# CPU.net
KiCad netlist of a schematic drawn in Altium Designer
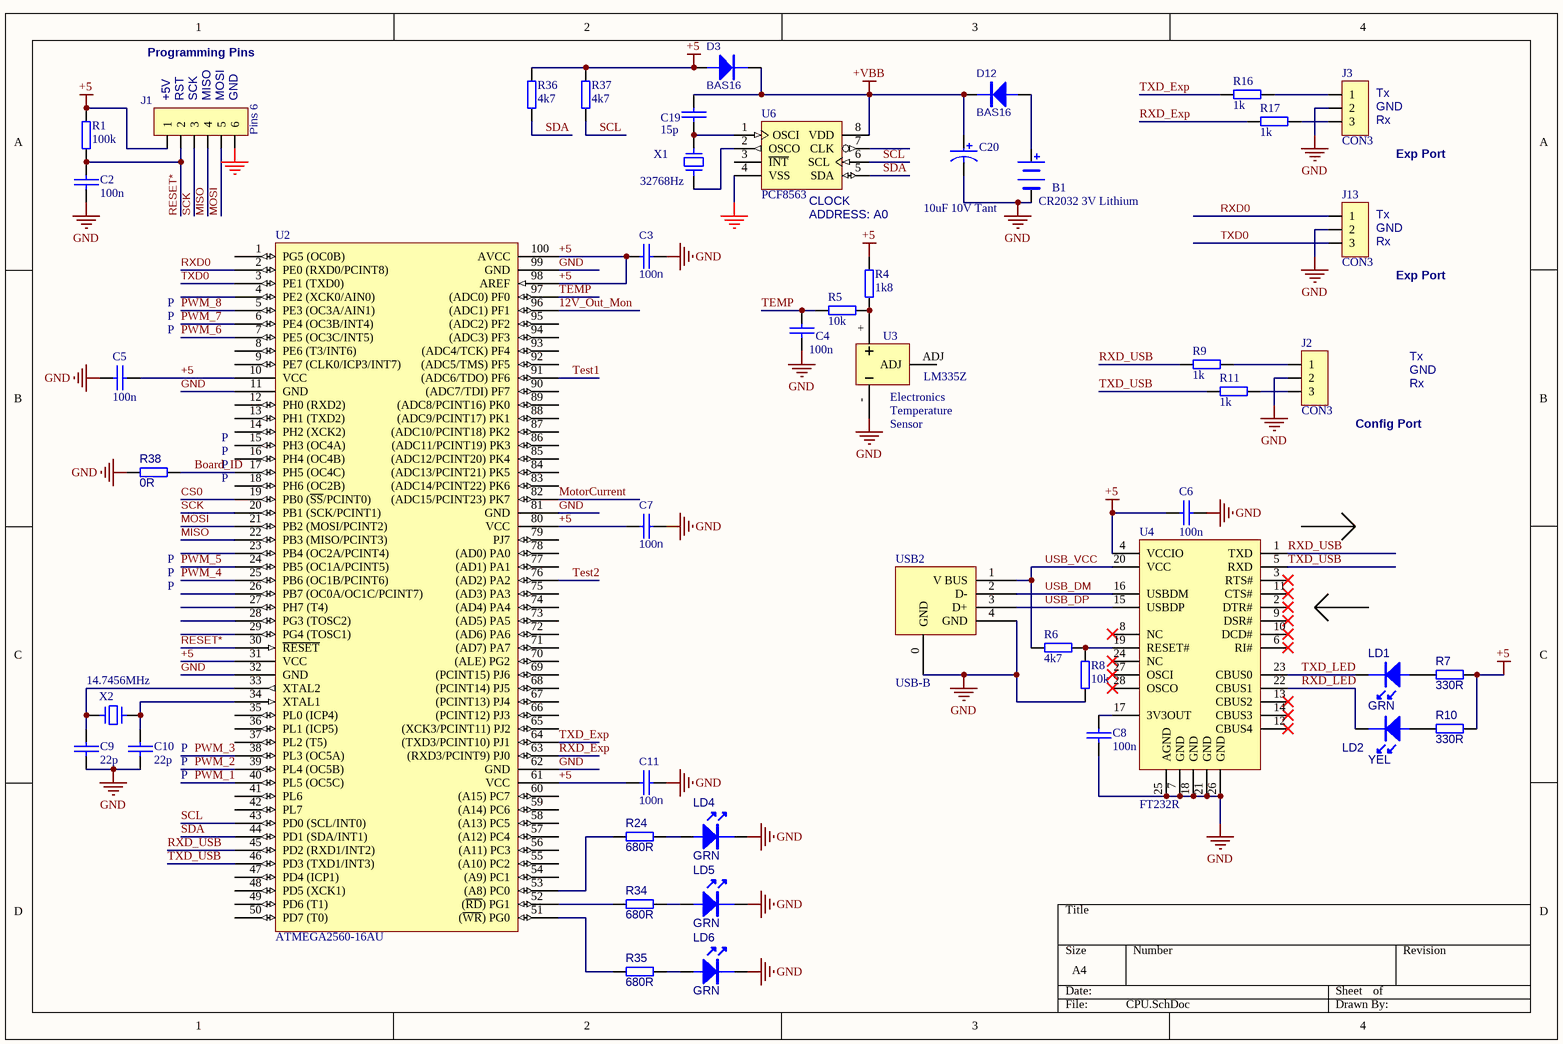
[diagram p0: CPU.SchDoc]

(export (version "E")
  (design (tool "Eeschema 10.0.6"))
  (components
    (comp (ref "B1")
      (value "CR2032 3V Lithium")
      (footprint "COINBATT6")
      (libsource (lib "*") (part "BATTERY"))
    )
    (comp (ref "C2") (value "100n") (footprint "0603") (libsource (lib "DEVICE") (part "CAP")))
    (comp (ref "C3") (value "100n") (footprint "0603") (libsource (lib "*") (part "CAP")))
    (comp (ref "C4") (value "100n") (footprint "0603") (libsource (lib "DEVICE") (part "CAP")))
    (comp (ref "C5") (value "100n") (footprint "0603") (libsource (lib "DEVICE") (part "CAP")))
    (comp (ref "C6") (value "100n") (footprint "0603") (libsource (lib "") (part "CAP_1")))
    (comp (ref "C7") (value "100n") (footprint "0603") (libsource (lib "*") (part "CAP")))
    (comp (ref "C8") (value "100n") (footprint "0603") (libsource (lib "") (part "CAP_1")))
    (comp (ref "C9") (value "22p") (footprint "0603") (libsource (lib "DEVICE") (part "CAP")))
    (comp (ref "C10") (value "22p") (footprint "0603") (libsource (lib "DEVICE") (part "CAP")))
    (comp (ref "C11") (value "100n") (footprint "0603") (libsource (lib "*") (part "CAP")))
    (comp (ref "C19") (value "15p") (footprint "0603") (libsource (lib "") (part "CAP_1")))
    (comp (ref "C20")
      (value "10uF 10V Tant")
      (footprint "SMD-TANT-A")
      (libsource (lib "DEVICE") (part "CAPACITOR POL-S"))
    )
    (comp (ref "D3") (value "BAS16") (footprint "SOT-23-bat54") (libsource (lib "*") (part "DIODE")))
    (comp (ref "D12") (value "BAS16") (footprint "SOT-23-bat54") (libsource (lib "*") (part "DIODE")))
    (comp (ref "J1") (value "Pins 6") (footprint "SIP6") (libsource (lib "*") (part "CON6")))
    (comp (ref "J2") (value "CON3") (footprint "SIP3") (libsource (lib "DEVICE") (part "CON3")))
    (comp (ref "J3") (value "CON3") (footprint "SIP3") (libsource (lib "DEVICE") (part "CON3")))
    (comp (ref "J13") (value "CON3") (footprint "SIP3") (libsource (lib "DEVICE") (part "CON3")))
    (comp (ref "LD1") (value "GRN") (footprint "0805DIODE") (libsource (lib "*") (part "LED")))
    (comp (ref "LD2") (value "YEL") (footprint "0805DIODE") (libsource (lib "*") (part "LED")))
    (comp (ref "LD4") (value "GRN") (footprint "0805DIODE") (libsource (lib "*") (part "LED")))
    (comp (ref "LD5") (value "GRN") (footprint "0805DIODE") (libsource (lib "*") (part "LED")))
    (comp (ref "LD6") (value "GRN") (footprint "0805DIODE") (libsource (lib "*") (part "LED")))
    (comp (ref "R1") (value "100k") (footprint "0603") (libsource (lib "DEVICE") (part "RES8")))
    (comp (ref "R4") (value "1k8") (footprint "0603") (libsource (lib "DEVICE") (part "RES8")))
    (comp (ref "R5") (value "10k") (footprint "0603") (libsource (lib "DEVICE") (part "RES8")))
    (comp (ref "R6") (value "4k7") (footprint "0603") (libsource (lib "DEVICE") (part "RES8")))
    (comp (ref "R7") (value "330R") (footprint "0603") (libsource (lib "DEVICE") (part "RES8")))
    (comp (ref "R8") (value "10k") (footprint "0603") (libsource (lib "DEVICE") (part "RES8")))
    (comp (ref "R9") (value "1k") (footprint "0603") (libsource (lib "DEVICE") (part "RES8")))
    (comp (ref "R10") (value "330R") (footprint "0603") (libsource (lib "DEVICE") (part "RES8")))
    (comp (ref "R11") (value "1k") (footprint "0603") (libsource (lib "DEVICE") (part "RES8")))
    (comp (ref "R16") (value "1k") (footprint "0603") (libsource (lib "DEVICE") (part "RES8")))
    (comp (ref "R17") (value "1k") (footprint "0603") (libsource (lib "DEVICE") (part "RES8")))
    (comp (ref "R24") (value "680R") (footprint "0603") (libsource (lib "DEVICE") (part "RES8")))
    (comp (ref "R34") (value "680R") (footprint "0603") (libsource (lib "DEVICE") (part "RES8")))
    (comp (ref "R35") (value "680R") (footprint "0603") (libsource (lib "DEVICE") (part "RES8")))
    (comp (ref "R36") (value "4k7") (footprint "0603") (libsource (lib "DEVICE") (part "RES8")))
    (comp (ref "R37") (value "4k7") (footprint "0603") (libsource (lib "DEVICE") (part "RES8")))
    (comp (ref "R38") (value "0R") (footprint "0603") (libsource (lib "DEVICE") (part "RES8")))
    (comp (ref "U2")
      (value "ATMEGA2560-16AU")
      (footprint "100T1_N")
      (libsource (lib "Atmel") (part "ATMEGA2560(TQFP100)"))
    )
    (comp (ref "U3") (value "LM335Z") (footprint "TO-92_LM335") (libsource (lib "D_LINEAR") (part "LM335Z")))
    (comp (ref "U4") (value "FT232R") (footprint "ssop28") (libsource (lib "FTDI") (part "FT232R")))
    (comp (ref "U6") (value "PCF8563") (footprint "so-8") (libsource (lib "PHILIPS") (part "PCF8563")))
    (comp (ref "USB2") (value "USB-B") (footprint "USB_BV") (libsource (lib "DEVICE") (part "USB-B")))
    (comp (ref "X1") (value "32768Hz") (footprint "XTAL32K") (libsource (lib "*") (part "CRYSTAL")))
    (comp (ref "X2") (value "14.7456MHz") (footprint "XTAL-V2") (libsource (lib "DEVICE") (part "CRYSTAL")))
  )
  (nets
    (net (code "1") (name "+5") (class "Default")
      (node (ref "C11") (pin "2") (pintype "passive"))
      (node (ref "C3") (pin "2") (pintype "passive"))
      (node (ref "C5") (pin "1") (pintype "passive"))
      (node (ref "C6") (pin "2") (pintype "passive"))
      (node (ref "C7") (pin "2") (pintype "passive"))
      (node (ref "D3") (pin "A") (pinfunction "A_A") (pintype "passive"))
      (node (ref "J1") (pin "1") (pinfunction "1_1") (pintype "passive"))
      (node (ref "R1") (pin "2") (pintype "passive"))
      (node (ref "R10") (pin "1") (pintype "passive"))
      (node (ref "R36") (pin "2") (pintype "passive"))
      (node (ref "R37") (pin "2") (pintype "passive"))
      (node (ref "R4") (pin "1") (pintype "passive"))
      (node (ref "R7") (pin "1") (pintype "passive"))
      (node (ref "U2") (pin "10") (pinfunction "VCC_10") (pintype "power_in"))
      (node (ref "U2") (pin "100") (pinfunction "AVCC_100") (pintype "power_in"))
      (node (ref "U2") (pin "31") (pinfunction "VCC_31") (pintype "power_in"))
      (node (ref "U2") (pin "61") (pinfunction "VCC_61") (pintype "power_in"))
      (node (ref "U2") (pin "80") (pinfunction "VCC_80") (pintype "power_in"))
      (node (ref "U2") (pin "98") (pinfunction "AREF_98") (pintype "input"))
      (node (ref "U4") (pin "4") (pinfunction "VCCIO_4") (pintype "passive"))
    )
    (net (code "2") (name "+VBB") (class "Default")
      (node (ref "C19") (pin "1") (pintype "passive"))
      (node (ref "C20") (pin "1") (pinfunction "1_1") (pintype "passive"))
      (node (ref "D12") (pin "K") (pinfunction "K_K") (pintype "passive"))
      (node (ref "D3") (pin "K") (pinfunction "K_K") (pintype "passive"))
      (node (ref "U6") (pin "8") (pinfunction "VDD_8") (pintype "power_in"))
    )
    (net (code "3") (name "/12V_Out_Mon") (class "Default")
      (node (ref "U2") (pin "96") (pinfunction "(ADC1)_PF1_96") (pintype "bidirectional"))
    )
    (net (code "4") (name "/Board_ID") (class "Default")
      (node (ref "R38") (pin "2") (pintype "passive"))
      (node (ref "U2") (pin "17") (pinfunction "PH5_(OC4C)_17") (pintype "bidirectional"))
    )
    (net (code "5") (name "/CS0") (class "Default")
      (node (ref "U2") (pin "19") (pinfunction "PB0_(~{SS}/PCINT0)_19") (pintype "bidirectional"))
    )
    (net (code "6") (name "/MISO") (class "Default")
      (node (ref "J1") (pin "4") (pinfunction "4_4") (pintype "passive"))
      (node (ref "U2") (pin "22") (pinfunction "PB3_(MISO/PCINT3)_22") (pintype "bidirectional"))
    )
    (net (code "7") (name "/MOSI") (class "Default")
      (node (ref "J1") (pin "5") (pinfunction "5_5") (pintype "passive"))
      (node (ref "U2") (pin "21") (pinfunction "PB2_(MOSI/PCINT2)_21") (pintype "bidirectional"))
    )
    (net (code "8") (name "/MotorCurrent") (class "Default")
      (node (ref "U2") (pin "82") (pinfunction "(ADC15/PCINT23)_PK7_82") (pintype "bidirectional"))
    )
    (net (code "9") (name "/PWM_1") (class "Default")
      (node (ref "U2") (pin "40") (pinfunction "PL5_(OC5C)_40") (pintype "bidirectional"))
    )
    (net (code "10") (name "/PWM_2") (class "Default")
      (node (ref "U2") (pin "39") (pinfunction "PL4_(OC5B)_39") (pintype "bidirectional"))
    )
    (net (code "11") (name "/PWM_3") (class "Default")
      (node (ref "U2") (pin "38") (pinfunction "PL3_(OC5A)_38") (pintype "bidirectional"))
    )
    (net (code "12") (name "/PWM_4") (class "Default")
      (node (ref "U2") (pin "25") (pinfunction "PB6_(OC1B/PCINT6)_25") (pintype "bidirectional"))
    )
    (net (code "13") (name "/PWM_5") (class "Default")
      (node (ref "U2") (pin "24") (pinfunction "PB5_(OC1A/PCINT5)_24") (pintype "bidirectional"))
    )
    (net (code "14") (name "/PWM_6") (class "Default")
      (node (ref "U2") (pin "7") (pinfunction "PE5_(OC3C/INT5)_7") (pintype "bidirectional"))
    )
    (net (code "15") (name "/PWM_7") (class "Default")
      (node (ref "U2") (pin "6") (pinfunction "PE4_(OC3B/INT4)_6") (pintype "bidirectional"))
    )
    (net (code "16") (name "/PWM_8") (class "Default")
      (node (ref "U2") (pin "5") (pinfunction "PE3_(OC3A/AIN1)_5") (pintype "bidirectional"))
    )
    (net (code "17") (name "/RESET*") (class "Default")
      (node (ref "C2") (pin "2") (pintype "passive"))
      (node (ref "J1") (pin "2") (pinfunction "2_2") (pintype "passive"))
      (node (ref "R1") (pin "1") (pintype "passive"))
      (node (ref "U2") (pin "30") (pinfunction "~{RESET}_30") (pintype "input"))
    )
    (net (code "18") (name "/RXD0") (class "Default")
      (node (ref "J13") (pin "1") (pinfunction "1_1") (pintype "passive"))
      (node (ref "U2") (pin "2") (pinfunction "PE0_(RXD0/PCINT8)_2") (pintype "bidirectional"))
    )
    (net (code "19") (name "/RXD_Exp") (class "Default")
      (node (ref "R17") (pin "1") (pintype "passive"))
      (node (ref "U2") (pin "63") (pinfunction "(RXD3/PCINT9)_PJ0_63") (pintype "bidirectional"))
    )
    (net (code "20") (name "/RXD_LED") (class "Default")
      (node (ref "LD2") (pin "K") (pintype "passive"))
      (node (ref "U4") (pin "22") (pinfunction "CBUS1_22") (pintype "passive"))
    )
    (net (code "21") (name "/RXD_USB") (class "Default")
      (node (ref "R9") (pin "1") (pintype "passive"))
      (node (ref "U2") (pin "45") (pinfunction "PD2_(RXD1/INT2)_45") (pintype "bidirectional"))
      (node (ref "U4") (pin "1") (pinfunction "TXD_1") (pintype "passive"))
    )
    (net (code "22") (name "/SCK") (class "Default")
      (node (ref "J1") (pin "3") (pinfunction "3_3") (pintype "passive"))
      (node (ref "U2") (pin "20") (pinfunction "PB1_(SCK/PCINT1)_20") (pintype "bidirectional"))
    )
    (net (code "23") (name "/SCL") (class "Default")
      (node (ref "R37") (pin "1") (pintype "passive"))
      (node (ref "U2") (pin "43") (pinfunction "PD0_(SCL/INT0)_43") (pintype "bidirectional"))
      (node (ref "U6") (pin "6") (pinfunction "SCL_6") (pintype "input"))
    )
    (net (code "24") (name "/SDA") (class "Default")
      (node (ref "R36") (pin "1") (pintype "passive"))
      (node (ref "U2") (pin "44") (pinfunction "PD1_(SDA/INT1)_44") (pintype "bidirectional"))
      (node (ref "U6") (pin "5") (pinfunction "SDA_5") (pintype "bidirectional"))
    )
    (net (code "25") (name "/TEMP") (class "Default")
      (node (ref "C4") (pin "1") (pintype "passive"))
      (node (ref "R5") (pin "1") (pintype "passive"))
      (node (ref "U2") (pin "97") (pinfunction "(ADC0)_PF0_97") (pintype "bidirectional"))
    )
    (net (code "26") (name "/TXD0") (class "Default")
      (node (ref "J13") (pin "3") (pinfunction "3_3") (pintype "passive"))
      (node (ref "U2") (pin "3") (pinfunction "PE1_(TXD0)_3") (pintype "bidirectional"))
    )
    (net (code "27") (name "/TXD_Exp") (class "Default")
      (node (ref "R16") (pin "1") (pintype "passive"))
      (node (ref "U2") (pin "64") (pinfunction "(TXD3/PCINT10)_PJ1_64") (pintype "bidirectional"))
    )
    (net (code "28") (name "/TXD_LED") (class "Default")
      (node (ref "LD1") (pin "K") (pintype "passive"))
      (node (ref "U4") (pin "23") (pinfunction "CBUS0_23") (pintype "passive"))
    )
    (net (code "29") (name "/TXD_USB") (class "Default")
      (node (ref "R11") (pin "1") (pintype "passive"))
      (node (ref "U2") (pin "46") (pinfunction "PD3_(TXD1/INT3)_46") (pintype "bidirectional"))
      (node (ref "U4") (pin "5") (pinfunction "RXD_5") (pintype "passive"))
    )
    (net (code "30") (name "/Test1") (class "Default")
      (node (ref "U2") (pin "91") (pinfunction "(ADC6/TDO)_PF6_91") (pintype "bidirectional"))
    )
    (net (code "31") (name "/Test2") (class "Default")
      (node (ref "U2") (pin "76") (pinfunction "(AD2)_PA2_76") (pintype "bidirectional"))
    )
    (net (code "32") (name "/USB_DM") (class "Default")
      (node (ref "U4") (pin "16") (pinfunction "USBDM_16") (pintype "passive"))
      (node (ref "USB2") (pin "2") (pinfunction "D-_2") (pintype "passive"))
    )
    (net (code "33") (name "/USB_DP") (class "Default")
      (node (ref "U4") (pin "15") (pinfunction "USBDP_15") (pintype "passive"))
      (node (ref "USB2") (pin "3") (pinfunction "D+_3") (pintype "passive"))
    )
    (net (code "34") (name "/USB_VCC") (class "Default")
      (node (ref "R6") (pin "1") (pintype "passive"))
      (node (ref "U4") (pin "20") (pinfunction "VCC_20") (pintype "passive"))
      (node (ref "USB2") (pin "1") (pinfunction "V_BUS_1") (pintype "passive"))
    )
    (net (code "35") (name "GND") (class "Default")
      (node (ref "B1") (pin "-") (pinfunction "-_-") (pintype "passive"))
      (node (ref "C10") (pin "2") (pintype "passive"))
      (node (ref "C11") (pin "1") (pintype "passive"))
      (node (ref "C2") (pin "1") (pintype "passive"))
      (node (ref "C20") (pin "2") (pinfunction "2_2") (pintype "passive"))
      (node (ref "C3") (pin "1") (pintype "passive"))
      (node (ref "C4") (pin "2") (pintype "passive"))
      (node (ref "C5") (pin "2") (pintype "passive"))
      (node (ref "C6") (pin "1") (pintype "passive"))
      (node (ref "C7") (pin "1") (pintype "passive"))
      (node (ref "C8") (pin "1") (pintype "passive"))
      (node (ref "C9") (pin "2") (pintype "passive"))
      (node (ref "J1") (pin "6") (pinfunction "6_6") (pintype "passive"))
      (node (ref "J13") (pin "2") (pinfunction "2_2") (pintype "passive"))
      (node (ref "J2") (pin "2") (pinfunction "2_2") (pintype "passive"))
      (node (ref "J3") (pin "2") (pinfunction "2_2") (pintype "passive"))
      (node (ref "LD4") (pin "K") (pintype "passive"))
      (node (ref "LD5") (pin "K") (pintype "passive"))
      (node (ref "LD6") (pin "K") (pintype "passive"))
      (node (ref "R38") (pin "1") (pintype "passive"))
      (node (ref "R8") (pin "1") (pintype "passive"))
      (node (ref "U2") (pin "11") (pinfunction "GND_11") (pintype "power_in"))
      (node (ref "U2") (pin "32") (pinfunction "GND_32") (pintype "power_in"))
      (node (ref "U2") (pin "62") (pinfunction "GND_62") (pintype "power_in"))
      (node (ref "U2") (pin "81") (pinfunction "GND_81") (pintype "power_in"))
      (node (ref "U2") (pin "99") (pinfunction "GND_99") (pintype "power_in"))
      (node (ref "U3") (pin "-") (pinfunction "-_-") (pintype "passive"))
      (node (ref "U4") (pin "18") (pinfunction "GND_18") (pintype "passive"))
      (node (ref "U4") (pin "21") (pinfunction "GND_21") (pintype "passive"))
      (node (ref "U4") (pin "25") (pinfunction "AGND_25") (pintype "passive"))
      (node (ref "U4") (pin "26") (pinfunction "GND_26") (pintype "passive"))
      (node (ref "U4") (pin "7") (pinfunction "GND_7") (pintype "passive"))
      (node (ref "U6") (pin "4") (pinfunction "VSS_4") (pintype "power_in"))
      (node (ref "USB2") (pin "0") (pinfunction "GND_0") (pintype "power_in"))
      (node (ref "USB2") (pin "4") (pinfunction "GND_4") (pintype "passive"))
    )
    (net (code "36") (name "Net-(B1-Pad+)") (class "Default")
      (node (ref "B1") (pin "+") (pinfunction "+_+") (pintype "passive"))
      (node (ref "D12") (pin "A") (pinfunction "A_A") (pintype "passive"))
    )
    (net (code "37") (name "Net-(J2-Pad1)") (class "Default")
      (node (ref "J2") (pin "1") (pinfunction "1_1") (pintype "passive"))
      (node (ref "R9") (pin "2") (pintype "passive"))
    )
    (net (code "38") (name "Net-(J2-Pad3)") (class "Default")
      (node (ref "J2") (pin "3") (pinfunction "3_3") (pintype "passive"))
      (node (ref "R11") (pin "2") (pintype "passive"))
    )
    (net (code "39") (name "Net-(J3-Pad1)") (class "Default")
      (node (ref "J3") (pin "1") (pinfunction "1_1") (pintype "passive"))
      (node (ref "R16") (pin "2") (pintype "passive"))
    )
    (net (code "40") (name "Net-(J3-Pad3)") (class "Default")
      (node (ref "J3") (pin "3") (pinfunction "3_3") (pintype "passive"))
      (node (ref "R17") (pin "2") (pintype "passive"))
    )
    (net (code "41") (name "Net-(LD1-PadA)") (class "Default")
      (node (ref "LD1") (pin "A") (pintype "passive"))
      (node (ref "R7") (pin "2") (pintype "passive"))
    )
    (net (code "42") (name "Net-(LD2-PadA)") (class "Default")
      (node (ref "LD2") (pin "A") (pintype "passive"))
      (node (ref "R10") (pin "2") (pintype "passive"))
    )
    (net (code "43") (name "Net-(LD4-PadA)") (class "Default")
      (node (ref "LD4") (pin "A") (pintype "passive"))
      (node (ref "R24") (pin "2") (pintype "passive"))
    )
    (net (code "44") (name "Net-(LD5-PadA)") (class "Default")
      (node (ref "LD5") (pin "A") (pintype "passive"))
      (node (ref "R34") (pin "2") (pintype "passive"))
    )
    (net (code "45") (name "Net-(LD6-PadA)") (class "Default")
      (node (ref "LD6") (pin "A") (pintype "passive"))
      (node (ref "R35") (pin "2") (pintype "passive"))
    )
    (net (code "46") (name "Net-(R4-Pad2)") (class "Default")
      (node (ref "R4") (pin "2") (pintype "passive"))
      (node (ref "R5") (pin "2") (pintype "passive"))
      (node (ref "U3") (pin "+") (pinfunction "+_+") (pintype "passive"))
    )
    (net (code "47") (name "Net-(U2-(A8)_PC0)") (class "Default")
      (node (ref "R24") (pin "1") (pintype "passive"))
      (node (ref "U2") (pin "53") (pinfunction "(A8)_PC0_53") (pintype "bidirectional"))
    )
    (net (code "48") (name "Net-(U2-(~{RD})_PG1)") (class "Default")
      (node (ref "R34") (pin "1") (pintype "passive"))
      (node (ref "U2") (pin "52") (pinfunction "(~{RD})_PG1_52") (pintype "bidirectional"))
    )
    (net (code "49") (name "Net-(U2-(~{WR})_PG0)") (class "Default")
      (node (ref "R35") (pin "1") (pintype "passive"))
      (node (ref "U2") (pin "51") (pinfunction "(~{WR})_PG0_51") (pintype "bidirectional"))
    )
    (net (code "50") (name "Net-(U2-XTAL1)") (class "Default")
      (node (ref "C10") (pin "1") (pintype "passive"))
      (node (ref "U2") (pin "34") (pinfunction "XTAL1_34") (pintype "input"))
      (node (ref "X2") (pin "1") (pintype "passive"))
    )
    (net (code "51") (name "Net-(U2-XTAL2)") (class "Default")
      (node (ref "C9") (pin "1") (pintype "passive"))
      (node (ref "U2") (pin "33") (pinfunction "XTAL2_33") (pintype "output"))
      (node (ref "X2") (pin "2") (pintype "passive"))
    )
    (net (code "52") (name "Net-(U4-3V3OUT)") (class "Default")
      (node (ref "C8") (pin "2") (pintype "passive"))
      (node (ref "U4") (pin "17") (pinfunction "3V3OUT_17") (pintype "passive"))
    )
    (net (code "53") (name "Net-(U4-RESET#)") (class "Default")
      (node (ref "R6") (pin "2") (pintype "passive"))
      (node (ref "R8") (pin "2") (pintype "passive"))
      (node (ref "U4") (pin "19") (pinfunction "RESET#_19") (pintype "passive"))
    )
    (net (code "54") (name "Net-(U6-OSCI)") (class "Default")
      (node (ref "C19") (pin "2") (pintype "passive"))
      (node (ref "U6") (pin "1") (pinfunction "OSCI_1") (pintype "input"))
      (node (ref "X1") (pin "2") (pintype "passive"))
    )
    (net (code "55") (name "Net-(U6-OSCO)") (class "Default")
      (node (ref "U6") (pin "2") (pinfunction "OSCO_2") (pintype "output"))
      (node (ref "X1") (pin "1") (pintype "passive"))
    )
    (net (code "56") (name "unconnected-(U2-(A9)_PC1-Pad54)") (class "Default")
      (node (ref "U2") (pin "54") (pinfunction "(A9)_PC1_54") (pintype "bidirectional"))
    )
    (net (code "57") (name "unconnected-(U2-(A10)_PC2-Pad55)") (class "Default")
      (node (ref "U2") (pin "55") (pinfunction "(A10)_PC2_55") (pintype "bidirectional"))
    )
    (net (code "58") (name "unconnected-(U2-(A11)_PC3-Pad56)") (class "Default")
      (node (ref "U2") (pin "56") (pinfunction "(A11)_PC3_56") (pintype "bidirectional"))
    )
    (net (code "59") (name "unconnected-(U2-(A12)_PC4-Pad57)") (class "Default")
      (node (ref "U2") (pin "57") (pinfunction "(A12)_PC4_57") (pintype "bidirectional"))
    )
    (net (code "60") (name "unconnected-(U2-(A13)_PC5-Pad58)") (class "Default")
      (node (ref "U2") (pin "58") (pinfunction "(A13)_PC5_58") (pintype "bidirectional"))
    )
    (net (code "61") (name "unconnected-(U2-(A14)_PC6-Pad59)") (class "Default")
      (node (ref "U2") (pin "59") (pinfunction "(A14)_PC6_59") (pintype "bidirectional"))
    )
    (net (code "62") (name "unconnected-(U2-(A15)_PC7-Pad60)") (class "Default")
      (node (ref "U2") (pin "60") (pinfunction "(A15)_PC7_60") (pintype "bidirectional"))
    )
    (net (code "63") (name "unconnected-(U2-(AD0)_PA0-Pad78)") (class "Default")
      (node (ref "U2") (pin "78") (pinfunction "(AD0)_PA0_78") (pintype "bidirectional"))
    )
    (net (code "64") (name "unconnected-(U2-(AD1)_PA1-Pad77)") (class "Default")
      (node (ref "U2") (pin "77") (pinfunction "(AD1)_PA1_77") (pintype "bidirectional"))
    )
    (net (code "65") (name "unconnected-(U2-(AD3)_PA3-Pad75)") (class "Default")
      (node (ref "U2") (pin "75") (pinfunction "(AD3)_PA3_75") (pintype "bidirectional"))
    )
    (net (code "66") (name "unconnected-(U2-(AD4)_PA4-Pad74)") (class "Default")
      (node (ref "U2") (pin "74") (pinfunction "(AD4)_PA4_74") (pintype "bidirectional"))
    )
    (net (code "67") (name "unconnected-(U2-(AD5)_PA5-Pad73)") (class "Default")
      (node (ref "U2") (pin "73") (pinfunction "(AD5)_PA5_73") (pintype "bidirectional"))
    )
    (net (code "68") (name "unconnected-(U2-(AD6)_PA6-Pad72)") (class "Default")
      (node (ref "U2") (pin "72") (pinfunction "(AD6)_PA6_72") (pintype "bidirectional"))
    )
    (net (code "69") (name "unconnected-(U2-(AD7)_PA7-Pad71)") (class "Default")
      (node (ref "U2") (pin "71") (pinfunction "(AD7)_PA7_71") (pintype "bidirectional"))
    )
    (net (code "70") (name "unconnected-(U2-(ADC2)_PF2-Pad95)") (class "Default")
      (node (ref "U2") (pin "95") (pinfunction "(ADC2)_PF2_95") (pintype "bidirectional"))
    )
    (net (code "71") (name "unconnected-(U2-(ADC3)_PF3-Pad94)") (class "Default")
      (node (ref "U2") (pin "94") (pinfunction "(ADC3)_PF3_94") (pintype "bidirectional"))
    )
    (net (code "72") (name "unconnected-(U2-(ADC4{slash}TCK)_PF4-Pad93)") (class "Default")
      (node (ref "U2") (pin "93") (pinfunction "(ADC4/TCK)_PF4_93") (pintype "bidirectional"))
    )
    (net (code "73") (name "unconnected-(U2-(ADC5{slash}TMS)_PF5-Pad92)") (class "Default")
      (node (ref "U2") (pin "92") (pinfunction "(ADC5/TMS)_PF5_92") (pintype "bidirectional"))
    )
    (net (code "74") (name "unconnected-(U2-(ADC7{slash}TDI)_PF7-Pad90)") (class "Default")
      (node (ref "U2") (pin "90") (pinfunction "(ADC7/TDI)_PF7_90") (pintype "bidirectional"))
    )
    (net (code "75") (name "unconnected-(U2-(ADC8{slash}PCINT16)_PK0-Pad89)") (class "Default")
      (node (ref "U2") (pin "89") (pinfunction "(ADC8/PCINT16)_PK0_89") (pintype "bidirectional"))
    )
    (net (code "76") (name "unconnected-(U2-(ADC9{slash}PCINT17)_PK1-Pad88)") (class "Default")
      (node (ref "U2") (pin "88") (pinfunction "(ADC9/PCINT17)_PK1_88") (pintype "bidirectional"))
    )
    (net (code "77") (name "unconnected-(U2-(ADC10{slash}PCINT18)_PK2-Pad87)") (class "Default")
      (node (ref "U2") (pin "87") (pinfunction "(ADC10/PCINT18)_PK2_87") (pintype "bidirectional"))
    )
    (net (code "78") (name "unconnected-(U2-(ADC11{slash}PCINT19)_PK3-Pad86)") (class "Default")
      (node (ref "U2") (pin "86") (pinfunction "(ADC11/PCINT19)_PK3_86") (pintype "bidirectional"))
    )
    (net (code "79") (name "unconnected-(U2-(ADC12{slash}PCINT20)_PK4-Pad85)") (class "Default")
      (node (ref "U2") (pin "85") (pinfunction "(ADC12/PCINT20)_PK4_85") (pintype "bidirectional"))
    )
    (net (code "80") (name "unconnected-(U2-(ADC13{slash}PCINT21)_PK5-Pad84)") (class "Default")
      (node (ref "U2") (pin "84") (pinfunction "(ADC13/PCINT21)_PK5_84") (pintype "bidirectional"))
    )
    (net (code "81") (name "unconnected-(U2-(ADC14{slash}PCINT22)_PK6-Pad83)") (class "Default")
      (node (ref "U2") (pin "83") (pinfunction "(ADC14/PCINT22)_PK6_83") (pintype "bidirectional"))
    )
    (net (code "82") (name "unconnected-(U2-(ALE)_PG2-Pad70)") (class "Default")
      (node (ref "U2") (pin "70") (pinfunction "(ALE)_PG2_70") (pintype "bidirectional"))
    )
    (net (code "83") (name "unconnected-(U2-(PCINT12)_PJ3-Pad66)") (class "Default")
      (node (ref "U2") (pin "66") (pinfunction "(PCINT12)_PJ3_66") (pintype "bidirectional"))
    )
    (net (code "84") (name "unconnected-(U2-(PCINT13)_PJ4-Pad67)") (class "Default")
      (node (ref "U2") (pin "67") (pinfunction "(PCINT13)_PJ4_67") (pintype "bidirectional"))
    )
    (net (code "85") (name "unconnected-(U2-(PCINT14)_PJ5-Pad68)") (class "Default")
      (node (ref "U2") (pin "68") (pinfunction "(PCINT14)_PJ5_68") (pintype "bidirectional"))
    )
    (net (code "86") (name "unconnected-(U2-(PCINT15)_PJ6-Pad69)") (class "Default")
      (node (ref "U2") (pin "69") (pinfunction "(PCINT15)_PJ6_69") (pintype "bidirectional"))
    )
    (net (code "87") (name "unconnected-(U2-(XCK3{slash}PCINT11)_PJ2-Pad65)") (class "Default")
      (node (ref "U2") (pin "65") (pinfunction "(XCK3/PCINT11)_PJ2_65") (pintype "bidirectional"))
    )
    (net (code "88") (name "unconnected-(U2-PB4_(OC2A{slash}PCINT4)-Pad23)") (class "Default")
      (node (ref "U2") (pin "23") (pinfunction "PB4_(OC2A/PCINT4)_23") (pintype "bidirectional"))
    )
    (net (code "89") (name "unconnected-(U2-PB7_(OC0A{slash}OC1C{slash}PCINT7)-Pad26)") (class "Default")
      (node (ref "U2") (pin "26") (pinfunction "PB7_(OC0A/OC1C/PCINT7)_26") (pintype "bidirectional"))
    )
    (net (code "90") (name "unconnected-(U2-PD4_(ICP1)-Pad47)") (class "Default")
      (node (ref "U2") (pin "47") (pinfunction "PD4_(ICP1)_47") (pintype "bidirectional"))
    )
    (net (code "91") (name "unconnected-(U2-PD5_(XCK1)-Pad48)") (class "Default")
      (node (ref "U2") (pin "48") (pinfunction "PD5_(XCK1)_48") (pintype "bidirectional"))
    )
    (net (code "92") (name "unconnected-(U2-PD6_(T1)-Pad49)") (class "Default")
      (node (ref "U2") (pin "49") (pinfunction "PD6_(T1)_49") (pintype "bidirectional"))
    )
    (net (code "93") (name "unconnected-(U2-PD7_(T0)-Pad50)") (class "Default")
      (node (ref "U2") (pin "50") (pinfunction "PD7_(T0)_50") (pintype "bidirectional"))
    )
    (net (code "94") (name "unconnected-(U2-PE2_(XCK0{slash}AIN0)-Pad4)") (class "Default")
      (node (ref "U2") (pin "4") (pinfunction "PE2_(XCK0/AIN0)_4") (pintype "bidirectional"))
    )
    (net (code "95") (name "unconnected-(U2-PE6_(T3{slash}INT6)-Pad8)") (class "Default")
      (node (ref "U2") (pin "8") (pinfunction "PE6_(T3/INT6)_8") (pintype "bidirectional"))
    )
    (net (code "96") (name "unconnected-(U2-PE7_(CLK0{slash}ICP3{slash}INT7)-Pad9)") (class "Default")
      (node (ref "U2") (pin "9") (pinfunction "PE7_(CLK0/ICP3/INT7)_9") (pintype "bidirectional"))
    )
    (net (code "97") (name "unconnected-(U2-PG3_(TOSC2)-Pad28)") (class "Default")
      (node (ref "U2") (pin "28") (pinfunction "PG3_(TOSC2)_28") (pintype "bidirectional"))
    )
    (net (code "98") (name "unconnected-(U2-PG4_(TOSC1)-Pad29)") (class "Default")
      (node (ref "U2") (pin "29") (pinfunction "PG4_(TOSC1)_29") (pintype "bidirectional"))
    )
    (net (code "99") (name "unconnected-(U2-PG5_(OC0B)-Pad1)") (class "Default")
      (node (ref "U2") (pin "1") (pinfunction "PG5_(OC0B)_1") (pintype "bidirectional"))
    )
    (net (code "100") (name "unconnected-(U2-PH0_(RXD2)-Pad12)") (class "Default")
      (node (ref "U2") (pin "12") (pinfunction "PH0_(RXD2)_12") (pintype "bidirectional"))
    )
    (net (code "101") (name "unconnected-(U2-PH1_(TXD2)-Pad13)") (class "Default")
      (node (ref "U2") (pin "13") (pinfunction "PH1_(TXD2)_13") (pintype "bidirectional"))
    )
    (net (code "102") (name "unconnected-(U2-PH2_(XCK2)-Pad14)") (class "Default")
      (node (ref "U2") (pin "14") (pinfunction "PH2_(XCK2)_14") (pintype "bidirectional"))
    )
    (net (code "103") (name "unconnected-(U2-PH3_(OC4A)-Pad15)") (class "Default")
      (node (ref "U2") (pin "15") (pinfunction "PH3_(OC4A)_15") (pintype "bidirectional"))
    )
    (net (code "104") (name "unconnected-(U2-PH4_(OC4B)-Pad16)") (class "Default")
      (node (ref "U2") (pin "16") (pinfunction "PH4_(OC4B)_16") (pintype "bidirectional"))
    )
    (net (code "105") (name "unconnected-(U2-PH6_(OC2B)-Pad18)") (class "Default")
      (node (ref "U2") (pin "18") (pinfunction "PH6_(OC2B)_18") (pintype "bidirectional"))
    )
    (net (code "106") (name "unconnected-(U2-PH7_(T4)-Pad27)") (class "Default")
      (node (ref "U2") (pin "27") (pinfunction "PH7_(T4)_27") (pintype "bidirectional"))
    )
    (net (code "107") (name "unconnected-(U2-PJ7-Pad79)") (class "Default")
      (node (ref "U2") (pin "79") (pinfunction "PJ7_79") (pintype "bidirectional"))
    )
    (net (code "108") (name "unconnected-(U2-PL0_(ICP4)-Pad35)") (class "Default")
      (node (ref "U2") (pin "35") (pinfunction "PL0_(ICP4)_35") (pintype "bidirectional"))
    )
    (net (code "109") (name "unconnected-(U2-PL1_(ICP5)-Pad36)") (class "Default")
      (node (ref "U2") (pin "36") (pinfunction "PL1_(ICP5)_36") (pintype "bidirectional"))
    )
    (net (code "110") (name "unconnected-(U2-PL2_(T5)-Pad37)") (class "Default")
      (node (ref "U2") (pin "37") (pinfunction "PL2_(T5)_37") (pintype "bidirectional"))
    )
    (net (code "111") (name "unconnected-(U2-PL6-Pad41)") (class "Default")
      (node (ref "U2") (pin "41") (pinfunction "PL6_41") (pintype "bidirectional"))
    )
    (net (code "112") (name "unconnected-(U2-PL7-Pad42)") (class "Default")
      (node (ref "U2") (pin "42") (pinfunction "PL7_42") (pintype "bidirectional"))
    )
    (net (code "113") (name "unconnected-(U3-PadADJ)") (class "Default")
      (node (ref "U3") (pin "ADJ") (pinfunction "ADJ_ADJ") (pintype "passive"))
    )
    (net (code "114") (name "unconnected-(U4-CBUS2-Pad13)") (class "Default")
      (node (ref "U4") (pin "13") (pinfunction "CBUS2_13") (pintype "passive+no_connect"))
    )
    (net (code "115") (name "unconnected-(U4-CBUS3-Pad14)") (class "Default")
      (node (ref "U4") (pin "14") (pinfunction "CBUS3_14") (pintype "passive+no_connect"))
    )
    (net (code "116") (name "unconnected-(U4-CBUS4-Pad12)") (class "Default")
      (node (ref "U4") (pin "12") (pinfunction "CBUS4_12") (pintype "passive+no_connect"))
    )
    (net (code "117") (name "unconnected-(U4-CTS#-Pad11)") (class "Default")
      (node (ref "U4") (pin "11") (pinfunction "CTS#_11") (pintype "passive+no_connect"))
    )
    (net (code "118") (name "unconnected-(U4-DCD#-Pad10)") (class "Default")
      (node (ref "U4") (pin "10") (pinfunction "DCD#_10") (pintype "passive+no_connect"))
    )
    (net (code "119") (name "unconnected-(U4-DSR#-Pad9)") (class "Default")
      (node (ref "U4") (pin "9") (pinfunction "DSR#_9") (pintype "passive+no_connect"))
    )
    (net (code "120") (name "unconnected-(U4-DTR#-Pad2)") (class "Default")
      (node (ref "U4") (pin "2") (pinfunction "DTR#_2") (pintype "passive+no_connect"))
    )
    (net (code "121") (name "unconnected-(U4-NC-Pad8)") (class "Default")
      (node (ref "U4") (pin "8") (pinfunction "NC_8") (pintype "passive+no_connect"))
    )
    (net (code "122") (name "unconnected-(U4-NC-Pad24)") (class "Default")
      (node (ref "U4") (pin "24") (pinfunction "NC_24") (pintype "passive+no_connect"))
    )
    (net (code "123") (name "unconnected-(U4-OSCI-Pad27)") (class "Default")
      (node (ref "U4") (pin "27") (pinfunction "OSCI_27") (pintype "passive+no_connect"))
    )
    (net (code "124") (name "unconnected-(U4-OSCO-Pad28)") (class "Default")
      (node (ref "U4") (pin "28") (pinfunction "OSCO_28") (pintype "passive+no_connect"))
    )
    (net (code "125") (name "unconnected-(U4-RI#-Pad6)") (class "Default")
      (node (ref "U4") (pin "6") (pinfunction "RI#_6") (pintype "passive+no_connect"))
    )
    (net (code "126") (name "unconnected-(U4-RTS#-Pad3)") (class "Default")
      (node (ref "U4") (pin "3") (pinfunction "RTS#_3") (pintype "passive+no_connect"))
    )
    (net (code "127") (name "unconnected-(U6-CLK-Pad7)") (class "Default")
      (node (ref "U6") (pin "7") (pinfunction "CLK_7") (pintype "output"))
    )
    (net (code "128") (name "unconnected-(U6-~{INT}-Pad3)") (class "Default")
      (node (ref "U6") (pin "3") (pinfunction "~{INT}_3") (pintype "open_collector"))
    )
  )
)
